# Ethernet.net
KiCad netlist of a schematic drawn in Altium Designer
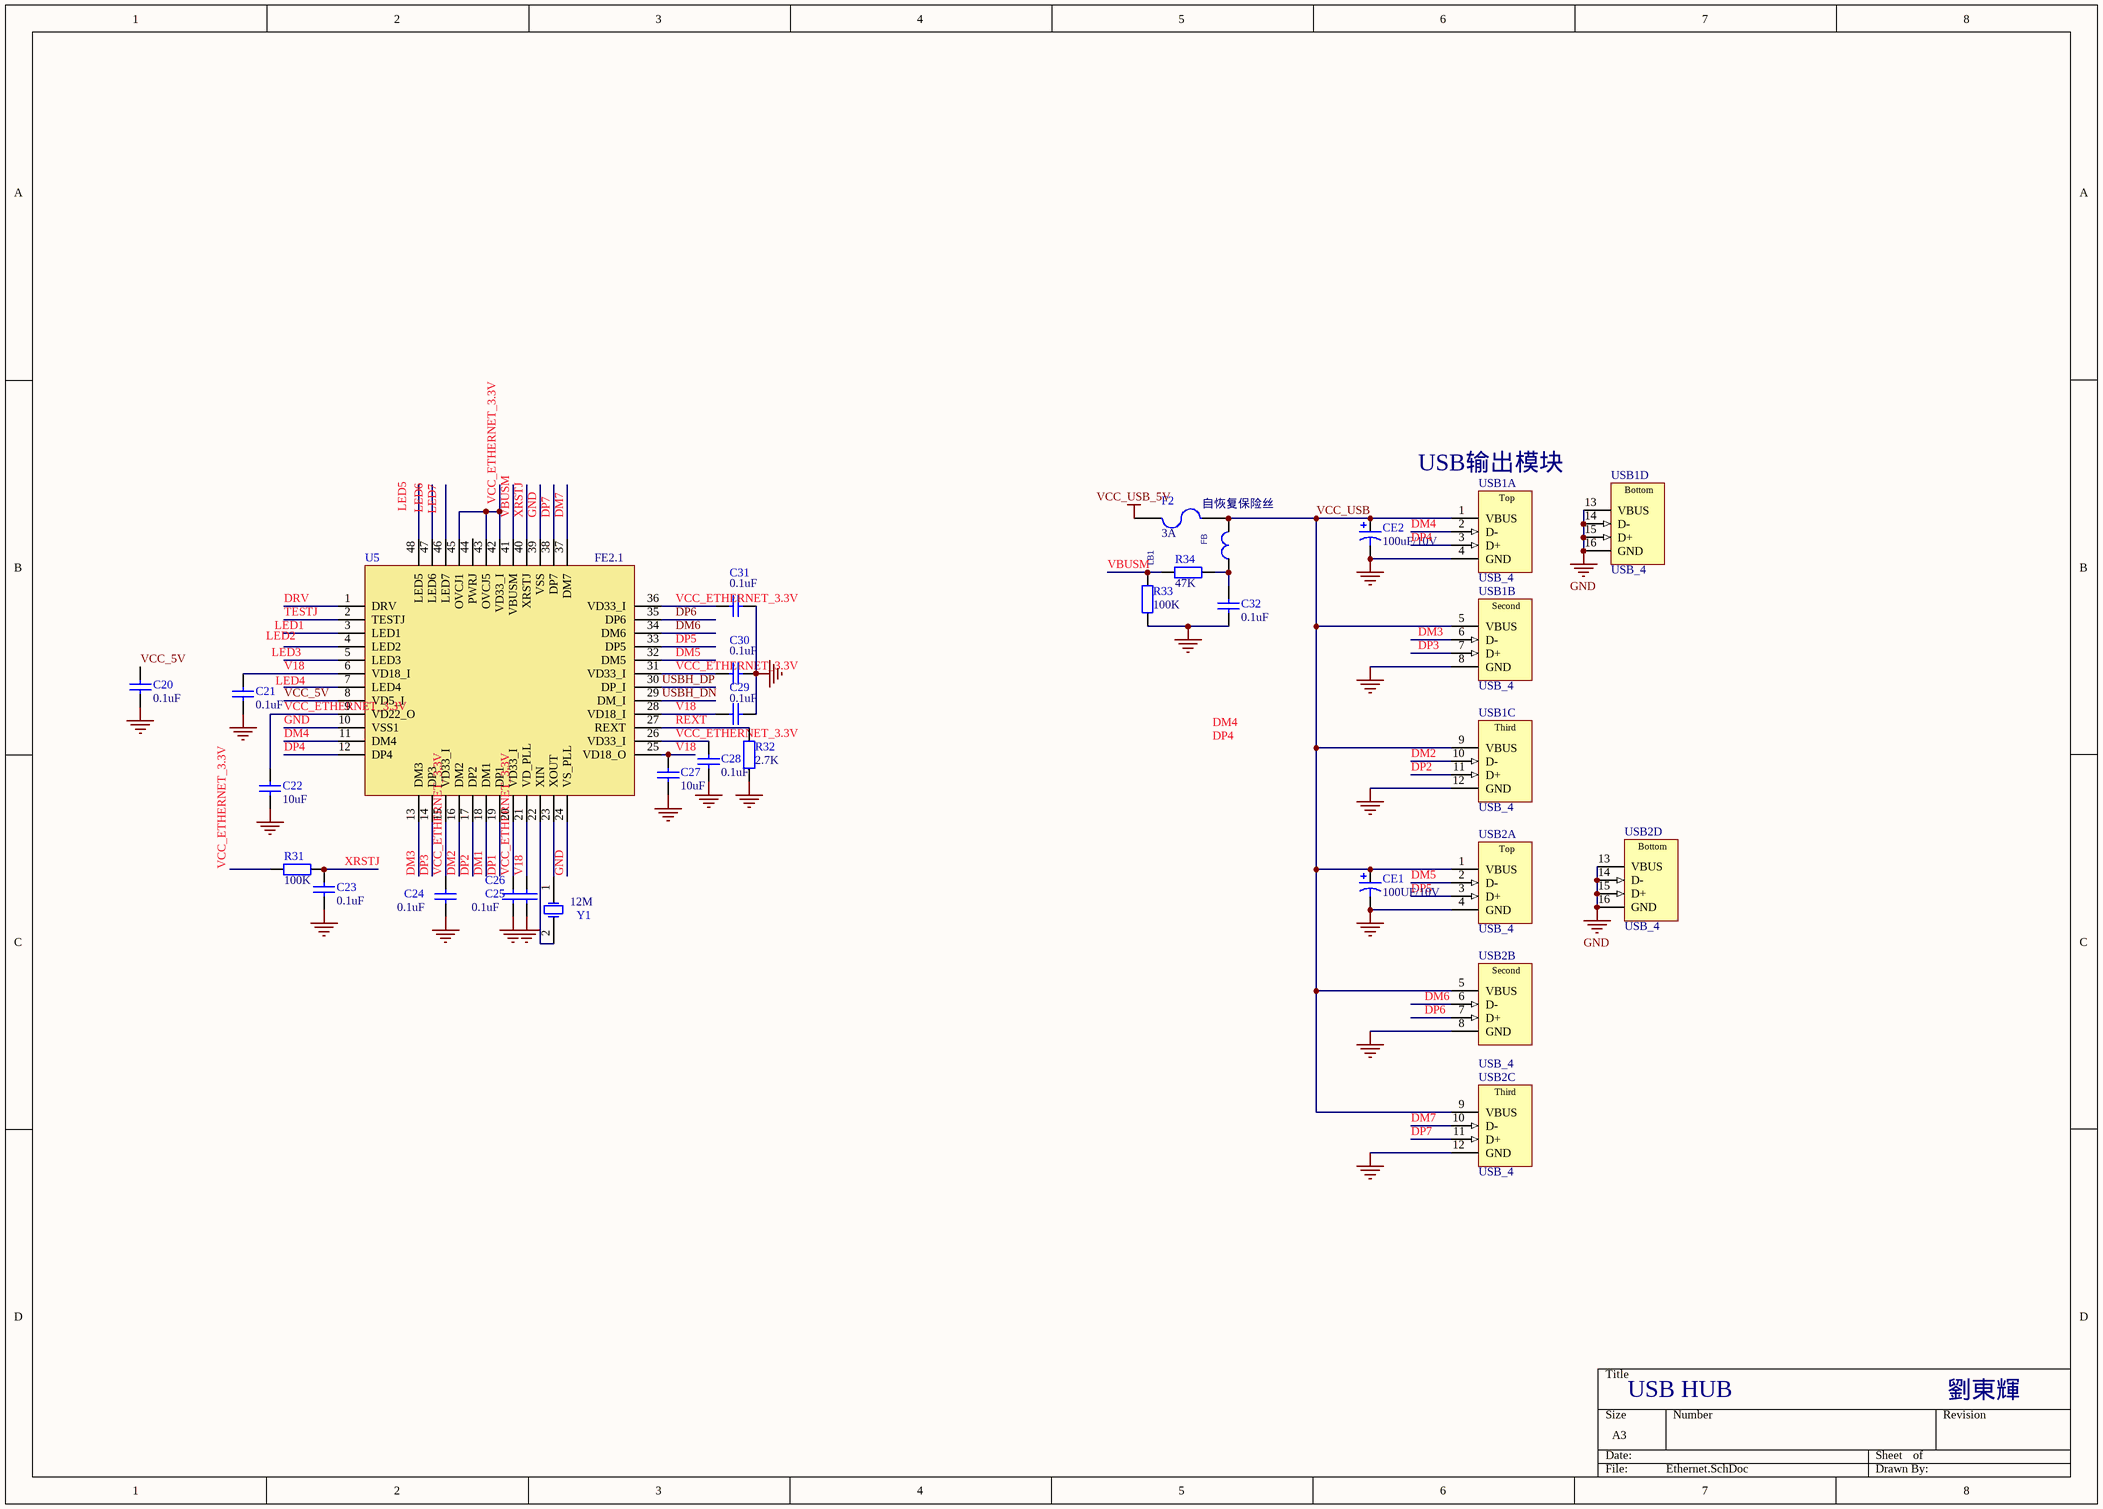
[diagram p0: Ethernet.SchDoc]

(export (version "E")
  (design (tool "Eeschema 10.0.6"))
  (components
    (comp (ref "C20")
      (value "0.1uF")
      (footprint "0805/2012 C3")
      (description "Capacitor")
      (fields (field (name "PUBLISHER") "*"))
      (libsource (lib "*") (part "Cap"))
    )
    (comp (ref "C21")
      (value "0.1uF")
      (footprint "0805/2012 C3")
      (description "Capacitor")
      (fields (field (name "PUBLISHER") "*"))
      (libsource (lib "*") (part "Cap"))
    )
    (comp (ref "C22")
      (value "10uF")
      (footprint "0805/2012 C3")
      (description "Capacitor")
      (fields (field (name "PUBLISHER") "*"))
      (libsource (lib "*") (part "Cap"))
    )
    (comp (ref "C23")
      (value "0.1uF")
      (footprint "0805/2012 C3")
      (description "Capacitor")
      (fields (field (name "PUBLISHER") "Altium Limited"))
      (libsource (lib "*") (part "Cap"))
    )
    (comp (ref "C24")
      (value "0.1uF")
      (footprint "0805/2012 C3")
      (description "Capacitor")
      (fields (field (name "PUBLISHER") "*"))
      (libsource (lib "*") (part "Cap"))
    )
    (comp (ref "C25")
      (value "0.1uF")
      (footprint "0805/2012 C3")
      (description "Capacitor")
      (fields (field (name "PUBLISHER") "Altium Limited"))
      (libsource (lib "*") (part "Cap"))
    )
    (comp (ref "C26")
      (value "0.1uF")
      (footprint "0805/2012 C3")
      (description "Capacitor")
      (fields (field (name "PUBLISHER") "Altium Limited"))
      (libsource (lib "*") (part "Cap"))
    )
    (comp (ref "C27")
      (value "10uF")
      (footprint "0805/2012 C3")
      (description "Capacitor")
      (fields (field (name "PUBLISHER") "*"))
      (libsource (lib "*") (part "Cap"))
    )
    (comp (ref "C28")
      (value "0.1uF")
      (footprint "0805/2012 C3")
      (description "Capacitor")
      (fields (field (name "PUBLISHER") "Altium Limited"))
      (libsource (lib "*") (part "Cap"))
    )
    (comp (ref "C29")
      (value "0.1uF")
      (footprint "0805/2012 C3")
      (description "Capacitor")
      (fields (field (name "PUBLISHER") "Altium Limited"))
      (libsource (lib "*") (part "Cap"))
    )
    (comp (ref "C30")
      (value "0.1uF")
      (footprint "0805/2012 C3")
      (description "Capacitor")
      (fields (field (name "PUBLISHER") "*"))
      (libsource (lib "*") (part "Cap"))
    )
    (comp (ref "C31")
      (value "0.1uF")
      (footprint "0805/2012 C3")
      (description "Capacitor")
      (fields (field (name "PUBLISHER") "Altium Limited"))
      (libsource (lib "*") (part "Cap"))
    )
    (comp (ref "C32")
      (value "0.1uF")
      (footprint "0805/2012 C3")
      (description "Capacitor")
      (fields (field (name "PUBLISHER") "Altium Limited"))
      (libsource (lib "*") (part "Cap"))
    )
    (comp (ref "CE1")
      (value "100UF/10V")
      (footprint "2312_6023-20_SMT-TAJ-F")
      (description "Polarized Capacitor (Radial)")
      (fields (field (name "PUBLISHER") "Altium Limited"))
      (libsource (lib "*") (part "Cap Pol1"))
    )
    (comp (ref "CE2")
      (value "100uF/10V")
      (footprint "2312_6023-20_SMT-TAJ-F")
      (description "Polarized Capacitor (Radial)")
      (fields (field (name "PUBLISHER") "*"))
      (libsource (lib "*") (part "Cap Pol1"))
    )
    (comp (ref "F2")
      (value "3A")
      (footprint "FUSR_BOURNS_MF-MSMF_STYLE1(H85)")
      (description "Fuse")
      (fields (field (name "PUBLISHER") "Altium Limited"))
      (libsource (lib "*") (part "Fuse 2"))
    )
    (comp (ref "LB1") (value "FB") (footprint "0805/2012 F3") (libsource (lib "*") (part "FB-0805")))
    (comp (ref "R31")
      (value "100K")
      (footprint "0805/2012 R3")
      (description "Resistor")
      (fields (field (name "PUBLISHER") "Altium Limited"))
      (libsource (lib "") (part "Res2_2"))
    )
    (comp (ref "R32")
      (value "2.7K")
      (footprint "0805/2012 R3")
      (description "Resistor")
      (fields (field (name "PUBLISHER") "*"))
      (libsource (lib "*") (part "Res2"))
    )
    (comp (ref "R33")
      (value "100K")
      (footprint "0805/2012 R3")
      (description "Resistor")
      (fields (field (name "PUBLISHER") "Altium Limited"))
      (libsource (lib "") (part "Res2_2"))
    )
    (comp (ref "R34")
      (value "47K")
      (footprint "0805/2012 R3")
      (description "Resistor")
      (fields (field (name "PUBLISHER") "Altium Limited"))
      (libsource (lib "") (part "Res2_1"))
    )
    (comp (ref "U5") (value "FE2.1") (footprint "LQFP-48L") (libsource (lib "*") (part "F2.1")))
    (comp (ref "USB1")
      (value "USB_4")
      (footprint "USB-3")
      (description "USB 1.1, Right Angle, Thru-Hole, A Type, Receptacle, 4x4x4x4 Position, Fourfold Stacked, Black")
      (fields (field (name "PUBLISHER") "Altium Limited"))
      (libsource (lib "USB.RJ45.SD.sim") (part "USB_4"))
    )
    (comp (ref "USB2")
      (value "USB_4")
      (footprint "USB-3")
      (description "USB 1.1, Right Angle, Thru-Hole, A Type, Receptacle, 4x4x4x4 Position, Fourfold Stacked, Black")
      (fields (field (name "PUBLISHER") "Altium Limited"))
      (libsource (lib "USB.RJ45.SD.sim") (part "USB_4"))
    )
    (comp (ref "Y1")
      (value "12M")
      (footprint "XTAL_CITIZEN_HCM49")
      (description "Crystal Oscillator")
      (fields (field (name "PUBLISHER") "*"))
      (libsource (lib "*") (part "XTAL"))
    )
  )
  (nets
    (net (code "1") (name "/DM1") (class "Default")
      (node (ref "U5") (pin "18") (pinfunction "DM1_18") (pintype "passive"))
    )
    (net (code "2") (name "/DM2") (class "Default")
      (node (ref "U5") (pin "16") (pinfunction "DM2_16") (pintype "passive"))
      (node (ref "USB1") (pin "10") (pinfunction "D-_10") (pintype "input"))
    )
    (net (code "3") (name "/DM3") (class "Default")
      (node (ref "U5") (pin "13") (pinfunction "DM3_13") (pintype "passive"))
      (node (ref "USB1") (pin "6") (pinfunction "D-_6") (pintype "input"))
    )
    (net (code "4") (name "/DM4") (class "Default")
      (node (ref "U5") (pin "11") (pinfunction "DM4_11") (pintype "passive"))
      (node (ref "USB1") (pin "2") (pinfunction "D-_2") (pintype "input"))
    )
    (net (code "5") (name "/DM5") (class "Default")
      (node (ref "U5") (pin "32") (pinfunction "DM5_32") (pintype "passive"))
      (node (ref "USB2") (pin "2") (pinfunction "D-_2") (pintype "input"))
    )
    (net (code "6") (name "/DM6") (class "Default")
      (node (ref "U5") (pin "34") (pinfunction "DM6_34") (pintype "passive"))
      (node (ref "USB2") (pin "6") (pinfunction "D-_6") (pintype "input"))
    )
    (net (code "7") (name "/DM7") (class "Default")
      (node (ref "U5") (pin "37") (pinfunction "DM7_37") (pintype "passive"))
      (node (ref "USB2") (pin "10") (pinfunction "D-_10") (pintype "input"))
    )
    (net (code "8") (name "/DP1") (class "Default")
      (node (ref "U5") (pin "19") (pinfunction "DP1_19") (pintype "passive"))
    )
    (net (code "9") (name "/DP2") (class "Default")
      (node (ref "U5") (pin "17") (pinfunction "DP2_17") (pintype "passive"))
      (node (ref "USB1") (pin "11") (pinfunction "D+_11") (pintype "input"))
    )
    (net (code "10") (name "/DP3") (class "Default")
      (node (ref "U5") (pin "14") (pinfunction "DP3_14") (pintype "passive"))
      (node (ref "USB1") (pin "7") (pinfunction "D+_7") (pintype "input"))
    )
    (net (code "11") (name "/DP4") (class "Default")
      (node (ref "U5") (pin "12") (pinfunction "DP4_12") (pintype "passive"))
      (node (ref "USB1") (pin "3") (pinfunction "D+_3") (pintype "input"))
    )
    (net (code "12") (name "/DP5") (class "Default")
      (node (ref "U5") (pin "33") (pinfunction "DP5_33") (pintype "passive"))
      (node (ref "USB2") (pin "3") (pinfunction "D+_3") (pintype "input"))
    )
    (net (code "13") (name "/DP6") (class "Default")
      (node (ref "U5") (pin "35") (pinfunction "DP6_35") (pintype "passive"))
      (node (ref "USB2") (pin "7") (pinfunction "D+_7") (pintype "input"))
    )
    (net (code "14") (name "/DP7") (class "Default")
      (node (ref "U5") (pin "38") (pinfunction "DP7_38") (pintype "passive"))
      (node (ref "USB2") (pin "11") (pinfunction "D+_11") (pintype "input"))
    )
    (net (code "15") (name "/DRV") (class "Default")
      (node (ref "U5") (pin "1") (pinfunction "DRV_1") (pintype "passive"))
    )
    (net (code "23") (name "/REXT") (class "Default")
      (node (ref "R32") (pin "2") (pinfunction "2_2") (pintype "passive"))
      (node (ref "U5") (pin "27") (pinfunction "REXT_27") (pintype "passive"))
    )
    (net (code "24") (name "/TESTJ") (class "Default")
      (node (ref "U5") (pin "2") (pinfunction "TESTJ_2") (pintype "passive"))
    )
    (net (code "25") (name "/USBH_DN") (class "Default")
      (node (ref "U5") (pin "29") (pinfunction "DM_I_29") (pintype "passive"))
    )
    (net (code "26") (name "/USBH_DP") (class "Default")
      (node (ref "U5") (pin "30") (pinfunction "DP_I_30") (pintype "passive"))
    )
    (net (code "27") (name "/V18") (class "Default")
      (node (ref "C21") (pin "2") (pinfunction "2_2") (pintype "passive"))
      (node (ref "C26") (pin "2") (pinfunction "2_2") (pintype "passive"))
      (node (ref "C27") (pin "2") (pinfunction "2_2") (pintype "passive"))
      (node (ref "C29") (pin "2") (pinfunction "2_2") (pintype "passive"))
      (node (ref "U5") (pin "21") (pinfunction "VD_PLL_21") (pintype "passive"))
      (node (ref "U5") (pin "25") (pinfunction "VD18_O_25") (pintype "passive"))
      (node (ref "U5") (pin "28") (pinfunction "VD18_I_28") (pintype "passive"))
      (node (ref "U5") (pin "6") (pinfunction "VD18_I_6") (pintype "passive"))
    )
    (net (code "28") (name "/VBUSM") (class "Default")
      (node (ref "R33") (pin "2") (pinfunction "2_2") (pintype "passive"))
      (node (ref "R34") (pin "2") (pinfunction "2_2") (pintype "passive"))
      (node (ref "U5") (pin "41") (pinfunction "VBUSM_41") (pintype "passive"))
    )
    (net (code "29") (name "/VCC_5V") (class "Default")
      (node (ref "C20") (pin "2") (pinfunction "2_2") (pintype "passive"))
      (node (ref "U5") (pin "8") (pinfunction "VD5_I_8") (pintype "passive"))
    )
    (net (code "30") (name "/VCC_ETHERNET_3.3V") (class "Default")
      (node (ref "C22") (pin "2") (pinfunction "2_2") (pintype "passive"))
      (node (ref "C24") (pin "2") (pinfunction "2_2") (pintype "passive"))
      (node (ref "C25") (pin "2") (pinfunction "2_2") (pintype "passive"))
      (node (ref "C28") (pin "2") (pinfunction "2_2") (pintype "passive"))
      (node (ref "C30") (pin "2") (pinfunction "2_2") (pintype "passive"))
      (node (ref "C31") (pin "2") (pinfunction "2_2") (pintype "passive"))
      (node (ref "R31") (pin "1") (pinfunction "1_1") (pintype "passive"))
      (node (ref "U5") (pin "15") (pinfunction "VD33_I_15") (pintype "passive"))
      (node (ref "U5") (pin "20") (pinfunction "VD33_I_20") (pintype "passive"))
      (node (ref "U5") (pin "26") (pinfunction "VD33_I_26") (pintype "passive"))
      (node (ref "U5") (pin "31") (pinfunction "VD33_I_31") (pintype "passive"))
      (node (ref "U5") (pin "36") (pinfunction "VD33_I_36") (pintype "passive"))
      (node (ref "U5") (pin "42") (pinfunction "VD33_I_42") (pintype "passive"))
      (node (ref "U5") (pin "43") (pinfunction "OVCJ5_43") (pintype "passive"))
      (node (ref "U5") (pin "45") (pinfunction "OVCJ1_45") (pintype "passive"))
      (node (ref "U5") (pin "9") (pinfunction "VD22_O_9") (pintype "passive"))
    )
    (net (code "31") (name "/VCC_USB") (class "Default")
      (node (ref "CE1") (pin "1") (pinfunction "1_1") (pintype "passive"))
      (node (ref "CE2") (pin "1") (pinfunction "1_1") (pintype "passive"))
      (node (ref "F2") (pin "1") (pinfunction "1_1") (pintype "passive"))
      (node (ref "LB1") (pin "2") (pinfunction "2_2") (pintype "passive"))
      (node (ref "USB1") (pin "1") (pinfunction "VBUS_1") (pintype "power_in"))
      (node (ref "USB1") (pin "5") (pinfunction "VBUS_5") (pintype "power_in"))
      (node (ref "USB1") (pin "9") (pinfunction "VBUS_9") (pintype "power_in"))
      (node (ref "USB2") (pin "1") (pinfunction "VBUS_1") (pintype "power_in"))
      (node (ref "USB2") (pin "5") (pinfunction "VBUS_5") (pintype "power_in"))
      (node (ref "USB2") (pin "9") (pinfunction "VBUS_9") (pintype "power_in"))
    )
    (net (code "32") (name "/XRSTJ") (class "Default")
      (node (ref "C23") (pin "2") (pinfunction "2_2") (pintype "passive"))
      (node (ref "R31") (pin "2") (pinfunction "2_2") (pintype "passive"))
      (node (ref "U5") (pin "40") (pinfunction "XRSTJ_40") (pintype "passive"))
    )
    (net (code "33") (name "GND") (class "Default")
      (node (ref "C20") (pin "1") (pinfunction "1_1") (pintype "passive"))
      (node (ref "C21") (pin "1") (pinfunction "1_1") (pintype "passive"))
      (node (ref "C22") (pin "1") (pinfunction "1_1") (pintype "passive"))
      (node (ref "C23") (pin "1") (pinfunction "1_1") (pintype "passive"))
      (node (ref "C24") (pin "1") (pinfunction "1_1") (pintype "passive"))
      (node (ref "C25") (pin "1") (pinfunction "1_1") (pintype "passive"))
      (node (ref "C26") (pin "1") (pinfunction "1_1") (pintype "passive"))
      (node (ref "C27") (pin "1") (pinfunction "1_1") (pintype "passive"))
      (node (ref "C28") (pin "1") (pinfunction "1_1") (pintype "passive"))
      (node (ref "C29") (pin "1") (pinfunction "1_1") (pintype "passive"))
      (node (ref "C30") (pin "1") (pinfunction "1_1") (pintype "passive"))
      (node (ref "C31") (pin "1") (pinfunction "1_1") (pintype "passive"))
      (node (ref "C32") (pin "1") (pinfunction "1_1") (pintype "passive"))
      (node (ref "CE1") (pin "2") (pinfunction "2_2") (pintype "passive"))
      (node (ref "CE2") (pin "2") (pinfunction "2_2") (pintype "passive"))
      (node (ref "R32") (pin "1") (pinfunction "1_1") (pintype "passive"))
      (node (ref "R33") (pin "1") (pinfunction "1_1") (pintype "passive"))
      (node (ref "U5") (pin "10") (pinfunction "VSS1_10") (pintype "passive"))
      (node (ref "U5") (pin "24") (pinfunction "VS_PLL_24") (pintype "passive"))
      (node (ref "U5") (pin "39") (pinfunction "VSS_39") (pintype "passive"))
      (node (ref "USB1") (pin "12") (pinfunction "GND_12") (pintype "power_in"))
      (node (ref "USB1") (pin "13") (pinfunction "VBUS_13") (pintype "power_in"))
      (node (ref "USB1") (pin "14") (pinfunction "D-_14") (pintype "input"))
      (node (ref "USB1") (pin "15") (pinfunction "D+_15") (pintype "input"))
      (node (ref "USB1") (pin "16") (pinfunction "GND_16") (pintype "power_in"))
      (node (ref "USB1") (pin "4") (pinfunction "GND_4") (pintype "power_in"))
      (node (ref "USB1") (pin "8") (pinfunction "GND_8") (pintype "power_in"))
      (node (ref "USB2") (pin "12") (pinfunction "GND_12") (pintype "power_in"))
      (node (ref "USB2") (pin "13") (pinfunction "VBUS_13") (pintype "power_in"))
      (node (ref "USB2") (pin "14") (pinfunction "D-_14") (pintype "input"))
      (node (ref "USB2") (pin "15") (pinfunction "D+_15") (pintype "input"))
      (node (ref "USB2") (pin "16") (pinfunction "GND_16") (pintype "power_in"))
      (node (ref "USB2") (pin "4") (pinfunction "GND_4") (pintype "power_in"))
      (node (ref "USB2") (pin "8") (pinfunction "GND_8") (pintype "power_in"))
    )
    (net (code "34") (name "Net-(C32-Pad2)") (class "Default")
      (node (ref "C32") (pin "2") (pinfunction "2_2") (pintype "passive"))
      (node (ref "LB1") (pin "1") (pinfunction "1_1") (pintype "passive"))
      (node (ref "R34") (pin "1") (pinfunction "1_1") (pintype "passive"))
    )
    (net (code "35") (name "Net-(U5-XIN)") (class "Default")
      (node (ref "U5") (pin "22") (pinfunction "XIN_22") (pintype "passive"))
      (node (ref "Y1") (pin "2") (pinfunction "OSC2_2") (pintype "passive"))
    )
    (net (code "36") (name "Net-(U5-XOUT)") (class "Default")
      (node (ref "U5") (pin "23") (pinfunction "XOUT_23") (pintype "passive"))
      (node (ref "Y1") (pin "1") (pinfunction "OSC1_1") (pintype "passive"))
    )
    (net (code "37") (name "VCC_USB_5V") (class "Default")
      (node (ref "F2") (pin "2") (pinfunction "2_2") (pintype "passive"))
    )
    (net (code "38") (name "unconnected-(U5-LED1-Pad3)") (class "Default")
      (node (ref "U5") (pin "3") (pinfunction "LED1_3") (pintype "passive"))
    )
    (net (code "39") (name "unconnected-(U5-LED2-Pad4)") (class "Default")
      (node (ref "U5") (pin "4") (pinfunction "LED2_4") (pintype "passive"))
    )
    (net (code "40") (name "unconnected-(U5-LED3-Pad5)") (class "Default")
      (node (ref "U5") (pin "5") (pinfunction "LED3_5") (pintype "passive"))
    )
    (net (code "41") (name "unconnected-(U5-LED4-Pad7)") (class "Default")
      (node (ref "U5") (pin "7") (pinfunction "LED4_7") (pintype "passive"))
    )
    (net (code "42") (name "unconnected-(U5-LED5-Pad48)") (class "Default")
      (node (ref "U5") (pin "48") (pinfunction "LED5_48") (pintype "passive"))
    )
    (net (code "43") (name "unconnected-(U5-LED6-Pad47)") (class "Default")
      (node (ref "U5") (pin "47") (pinfunction "LED6_47") (pintype "passive"))
    )
    (net (code "44") (name "unconnected-(U5-LED7-Pad46)") (class "Default")
      (node (ref "U5") (pin "46") (pinfunction "LED7_46") (pintype "passive"))
    )
    (net (code "45") (name "unconnected-(U5-PWRJ-Pad44)") (class "Default")
      (node (ref "U5") (pin "44") (pinfunction "PWRJ_44") (pintype "passive"))
    )
  )
)
